# squall-blees-board.net
KiCad netlist of a schematic drawn in EAGLE
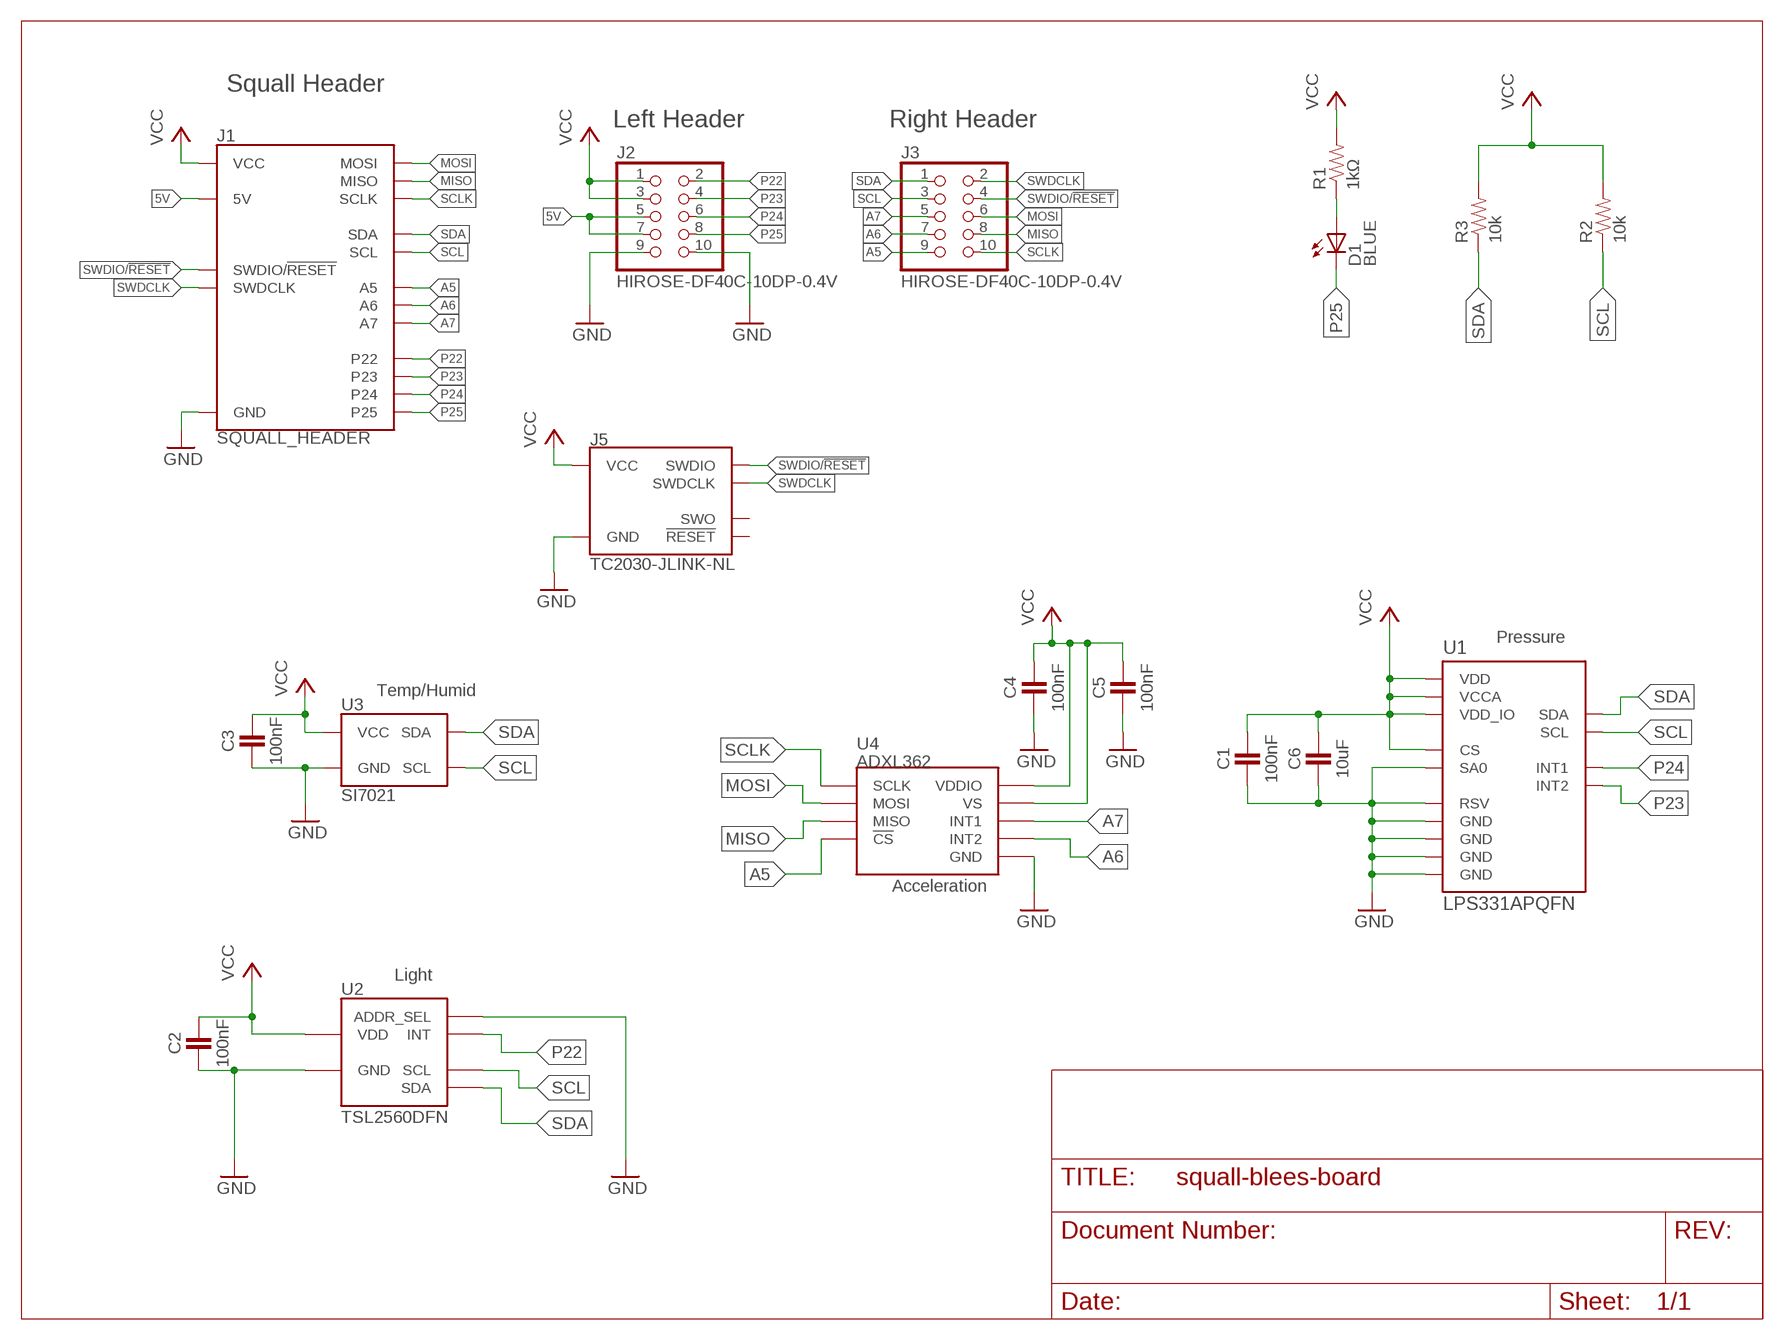
[diagram p0: schematic, sheet 1]

(export (version "E")
  (design (tool "Eeschema 10.0.6"))
  (components
    (comp (ref "C1")
      (value "100nF")
      (footprint "eagle-import:0402_CAP")
      (libsource (lib "eagle-import") (part "CAPACITOR"))
    )
    (comp (ref "C2")
      (value "100nF")
      (footprint "eagle-import:0402_CAP")
      (libsource (lib "eagle-import") (part "CAPACITOR"))
    )
    (comp (ref "C3")
      (value "100nF")
      (footprint "eagle-import:0402_CAP")
      (libsource (lib "eagle-import") (part "CAPACITOR"))
    )
    (comp (ref "C4")
      (value "100nF")
      (footprint "eagle-import:0402_CAP")
      (libsource (lib "eagle-import") (part "CAPACITOR"))
    )
    (comp (ref "C5")
      (value "100nF")
      (footprint "eagle-import:0402_CAP")
      (libsource (lib "eagle-import") (part "CAPACITOR"))
    )
    (comp (ref "C6")
      (value "10uF")
      (footprint "eagle-import:0603_CAP")
      (libsource (lib "eagle-import") (part "CAPACITOR0603_CAP"))
    )
    (comp (ref "D1")
      (value "BLUE")
      (footprint "eagle-import:LED-0603")
      (libsource (lib "eagle-import") (part "LED0603"))
    )
    (comp (ref "J1")
      (value "SQUALL_HEADER")
      (footprint "eagle-import:SQUALL_HEADER")
      (libsource (lib "eagle-import") (part "SQUALL_HEADER"))
    )
    (comp (ref "J2")
      (value "HIROSE-DF40C-10DP-0.4V")
      (footprint "eagle-import:2X5_SMD_0.4MM")
      (libsource (lib "eagle-import") (part "HIROSE-DF40C-10DP-0.4V"))
    )
    (comp (ref "J3")
      (value "HIROSE-DF40C-10DP-0.4V")
      (footprint "eagle-import:2X5_SMD_0.4MM")
      (libsource (lib "eagle-import") (part "HIROSE-DF40C-10DP-0.4V"))
    )
    (comp (ref "J5")
      (value "TC2030-JLINK-NL")
      (footprint "eagle-import:TC2030-IDC-NL")
      (libsource (lib "eagle-import") (part "TC2030-JLINK-NL"))
    )
    (comp (ref "R1")
      (value "1kΩ")
      (footprint "eagle-import:0402_RES")
      (libsource (lib "eagle-import") (part "RESISTOR0402_RES"))
    )
    (comp (ref "R2")
      (value "10k")
      (footprint "eagle-import:0402_RES")
      (libsource (lib "eagle-import") (part "RESISTOR0402_RES"))
    )
    (comp (ref "R3")
      (value "10k")
      (footprint "eagle-import:0402_RES")
      (libsource (lib "eagle-import") (part "RESISTOR0402_RES"))
    )
    (comp (ref "U1")
      (value "LPS331APQFN")
      (footprint "eagle-import:HCLGA-16L")
      (libsource (lib "eagle-import") (part "LPS331APQFN"))
    )
    (comp (ref "U2")
      (value "TSL2560DFN")
      (footprint "eagle-import:DFN2")
      (libsource (lib "eagle-import") (part "TSL2560DFN"))
    )
    (comp (ref "U3")
      (value "SI7021")
      (footprint "eagle-import:DFN-6_3MM")
      (libsource (lib "eagle-import") (part "SI7021"))
    )
    (comp (ref "U4")
      (value "ADXL362")
      (footprint "eagle-import:ADXL362")
      (libsource (lib "eagle-import") (part "ADXL362"))
    )
  )
  (nets
    (net (code "1") (name "/SWDIO{slash}~{RESET}") (class "Default")
      (node (ref "J1") (pin "B4") (pinfunction "SWDIO/~{RESET}_B4") (pintype "bidirectional"))
      (node (ref "J3") (pin "4") (pinfunction "4_4") (pintype "passive"))
      (node (ref "J5") (pin "2") (pinfunction "SWDIO_2") (pintype "bidirectional"))
    )
    (net (code "2") (name "5V") (class "Default")
      (node (ref "J1") (pin "A5") (pinfunction "5V_A5") (pintype "bidirectional"))
      (node (ref "J1") (pin "A7") (pinfunction "5V_A7") (pintype "bidirectional"))
      (node (ref "J2") (pin "5") (pinfunction "5_5") (pintype "passive"))
      (node (ref "J2") (pin "7") (pinfunction "7_7") (pintype "passive"))
    )
    (net (code "3") (name "A5") (class "Default")
      (node (ref "J1") (pin "B9") (pinfunction "A5_B9") (pintype "bidirectional"))
      (node (ref "J3") (pin "9") (pinfunction "9_9") (pintype "passive"))
      (node (ref "U4") (pin "P$8") (pinfunction "~{CS}_P$8") (pintype "bidirectional"))
    )
    (net (code "4") (name "A6") (class "Default")
      (node (ref "J1") (pin "B7") (pinfunction "A6_B7") (pintype "bidirectional"))
      (node (ref "J3") (pin "7") (pinfunction "7_7") (pintype "passive"))
      (node (ref "U4") (pin "P$9") (pinfunction "INT2_P$9") (pintype "bidirectional"))
    )
    (net (code "5") (name "A7") (class "Default")
      (node (ref "J1") (pin "B5") (pinfunction "A7_B5") (pintype "bidirectional"))
      (node (ref "J3") (pin "5") (pinfunction "5_5") (pintype "passive"))
      (node (ref "U4") (pin "P$11") (pinfunction "INT1_P$11") (pintype "bidirectional"))
    )
    (net (code "6") (name "GND") (class "Default")
      (node (ref "C1") (pin "2") (pinfunction "2_2") (pintype "bidirectional"))
      (node (ref "C2") (pin "2") (pinfunction "2_2") (pintype "bidirectional"))
      (node (ref "C3") (pin "2") (pinfunction "2_2") (pintype "bidirectional"))
      (node (ref "C4") (pin "2") (pinfunction "2_2") (pintype "bidirectional"))
      (node (ref "C5") (pin "2") (pinfunction "2_2") (pintype "bidirectional"))
      (node (ref "C6") (pin "2") (pinfunction "2_2") (pintype "bidirectional"))
      (node (ref "J1") (pin "A10") (pinfunction "GND_A10") (pintype "bidirectional"))
      (node (ref "J1") (pin "A9") (pinfunction "GND_A9") (pintype "bidirectional"))
      (node (ref "J2") (pin "10") (pinfunction "10_10") (pintype "passive"))
      (node (ref "J2") (pin "9") (pinfunction "9_9") (pintype "passive"))
      (node (ref "J5") (pin "5") (pinfunction "GND_5") (pintype "bidirectional"))
      (node (ref "U1") (pin "10") (pinfunction "RSV_10") (pintype "power_in"))
      (node (ref "U1") (pin "12") (pinfunction "GND_12") (pintype "power_in"))
      (node (ref "U1") (pin "13") (pinfunction "GND_13") (pintype "power_in"))
      (node (ref "U1") (pin "16") (pinfunction "GND_16") (pintype "power_in"))
      (node (ref "U1") (pin "5") (pinfunction "GND_5") (pintype "power_in"))
      (node (ref "U1") (pin "7") (pinfunction "SA0_7") (pintype "input"))
      (node (ref "U2") (pin "2") (pinfunction "ADDR_SEL_2") (pintype "bidirectional"))
      (node (ref "U2") (pin "3") (pinfunction "GND_3") (pintype "power_in"))
      (node (ref "U3") (pin "2") (pinfunction "GND_2") (pintype "bidirectional"))
      (node (ref "U4") (pin "P$12") (pinfunction "GND_P$12") (pintype "bidirectional"))
      (node (ref "U4") (pin "P$13") (pinfunction "GND_P$13") (pintype "bidirectional"))
      (node (ref "U4") (pin "P$16") (pinfunction "GND_P$16") (pintype "bidirectional"))
    )
    (net (code "7") (name "MISO") (class "Default")
      (node (ref "J1") (pin "B8") (pinfunction "MISO_B8") (pintype "bidirectional"))
      (node (ref "J3") (pin "8") (pinfunction "8_8") (pintype "passive"))
      (node (ref "U4") (pin "P$7") (pinfunction "MISO_P$7") (pintype "bidirectional"))
    )
    (net (code "8") (name "MOSI") (class "Default")
      (node (ref "J1") (pin "B6") (pinfunction "MOSI_B6") (pintype "bidirectional"))
      (node (ref "J3") (pin "6") (pinfunction "6_6") (pintype "passive"))
      (node (ref "U4") (pin "P$6") (pinfunction "MOSI_P$6") (pintype "bidirectional"))
    )
    (net (code "9") (name "Net-(D1-PadA)") (class "Default")
      (node (ref "D1") (pin "A") (pinfunction "A_A") (pintype "passive"))
      (node (ref "R1") (pin "1") (pinfunction "1_1") (pintype "passive"))
    )
    (net (code "10") (name "P22") (class "Default")
      (node (ref "J1") (pin "A2") (pinfunction "P22_A2") (pintype "bidirectional"))
      (node (ref "J2") (pin "2") (pinfunction "2_2") (pintype "passive"))
      (node (ref "U2") (pin "5") (pinfunction "INT_5") (pintype "bidirectional"))
    )
    (net (code "11") (name "P23") (class "Default")
      (node (ref "J1") (pin "A4") (pinfunction "P23_A4") (pintype "bidirectional"))
      (node (ref "J2") (pin "4") (pinfunction "4_4") (pintype "passive"))
      (node (ref "U1") (pin "9") (pinfunction "INT2_9") (pintype "bidirectional"))
    )
    (net (code "12") (name "P24") (class "Default")
      (node (ref "J1") (pin "A6") (pinfunction "P24_A6") (pintype "bidirectional"))
      (node (ref "J2") (pin "6") (pinfunction "6_6") (pintype "passive"))
      (node (ref "U1") (pin "11") (pinfunction "INT1_11") (pintype "bidirectional"))
    )
    (net (code "13") (name "P25") (class "Default")
      (node (ref "D1") (pin "C") (pinfunction "C_C") (pintype "passive"))
      (node (ref "J1") (pin "A8") (pinfunction "P25_A8") (pintype "bidirectional"))
      (node (ref "J2") (pin "8") (pinfunction "8_8") (pintype "passive"))
    )
    (net (code "14") (name "SCL") (class "Default")
      (node (ref "J1") (pin "B3") (pinfunction "SCL_B3") (pintype "bidirectional"))
      (node (ref "J3") (pin "3") (pinfunction "3_3") (pintype "passive"))
      (node (ref "R2") (pin "1") (pinfunction "1_1") (pintype "passive"))
      (node (ref "U1") (pin "4") (pinfunction "SCL_4") (pintype "bidirectional"))
      (node (ref "U2") (pin "4") (pinfunction "SCL_4") (pintype "bidirectional"))
      (node (ref "U3") (pin "6") (pinfunction "SCL_6") (pintype "bidirectional"))
    )
    (net (code "15") (name "SCLK") (class "Default")
      (node (ref "J1") (pin "B10") (pinfunction "SCLK_B10") (pintype "bidirectional"))
      (node (ref "J3") (pin "10") (pinfunction "10_10") (pintype "passive"))
      (node (ref "U4") (pin "P$4") (pinfunction "SCLK_P$4") (pintype "bidirectional"))
    )
    (net (code "16") (name "SDA") (class "Default")
      (node (ref "J1") (pin "B1") (pinfunction "SDA_B1") (pintype "bidirectional"))
      (node (ref "J3") (pin "1") (pinfunction "1_1") (pintype "passive"))
      (node (ref "R3") (pin "1") (pinfunction "1_1") (pintype "passive"))
      (node (ref "U1") (pin "6") (pinfunction "SDA_6") (pintype "bidirectional"))
      (node (ref "U2") (pin "6") (pinfunction "SDA_6") (pintype "bidirectional"))
      (node (ref "U3") (pin "1") (pinfunction "SDA_1") (pintype "bidirectional"))
    )
    (net (code "17") (name "SWDCLK") (class "Default")
      (node (ref "J1") (pin "B2") (pinfunction "SWDCLK_B2") (pintype "bidirectional"))
      (node (ref "J3") (pin "2") (pinfunction "2_2") (pintype "passive"))
      (node (ref "J5") (pin "4") (pinfunction "SWDCLK_4") (pintype "bidirectional"))
    )
    (net (code "18") (name "VCC") (class "Default")
      (node (ref "C1") (pin "1") (pinfunction "1_1") (pintype "bidirectional"))
      (node (ref "C2") (pin "1") (pinfunction "1_1") (pintype "bidirectional"))
      (node (ref "C3") (pin "1") (pinfunction "1_1") (pintype "bidirectional"))
      (node (ref "C4") (pin "1") (pinfunction "1_1") (pintype "bidirectional"))
      (node (ref "C5") (pin "1") (pinfunction "1_1") (pintype "bidirectional"))
      (node (ref "C6") (pin "1") (pinfunction "1_1") (pintype "bidirectional"))
      (node (ref "J1") (pin "A1") (pinfunction "VCC_A1") (pintype "bidirectional"))
      (node (ref "J1") (pin "A3") (pinfunction "VCC_A3") (pintype "bidirectional"))
      (node (ref "J2") (pin "1") (pinfunction "1_1") (pintype "passive"))
      (node (ref "J2") (pin "3") (pinfunction "3_3") (pintype "passive"))
      (node (ref "J5") (pin "1") (pinfunction "VCC_1") (pintype "bidirectional"))
      (node (ref "R1") (pin "2") (pinfunction "2_2") (pintype "passive"))
      (node (ref "R2") (pin "2") (pinfunction "2_2") (pintype "passive"))
      (node (ref "R3") (pin "2") (pinfunction "2_2") (pintype "passive"))
      (node (ref "U1") (pin "1") (pinfunction "VDD_IO_1") (pintype "power_in"))
      (node (ref "U1") (pin "14") (pinfunction "VDD_14") (pintype "power_in"))
      (node (ref "U1") (pin "15") (pinfunction "VCCA_15") (pintype "power_in"))
      (node (ref "U1") (pin "8") (pinfunction "CS_8") (pintype "input"))
      (node (ref "U2") (pin "1") (pinfunction "VDD_1") (pintype "power_in"))
      (node (ref "U3") (pin "5") (pinfunction "VCC_5") (pintype "bidirectional"))
      (node (ref "U4") (pin "P$1") (pinfunction "VDDIO_P$1") (pintype "bidirectional"))
      (node (ref "U4") (pin "P$14") (pinfunction "VS_P$14") (pintype "bidirectional"))
    )
    (net (code "19") (name "unconnected-(J5-SWO-Pad6)") (class "Default")
      (node (ref "J5") (pin "6") (pinfunction "SWO_6") (pintype "bidirectional"))
    )
    (net (code "20") (name "unconnected-(J5-~{RESET}-Pad3)") (class "Default")
      (node (ref "J5") (pin "3") (pinfunction "~{RESET}_3") (pintype "bidirectional"))
    )
  )
)
